# Power.net
KiCad netlist of a schematic drawn in Altium Designer
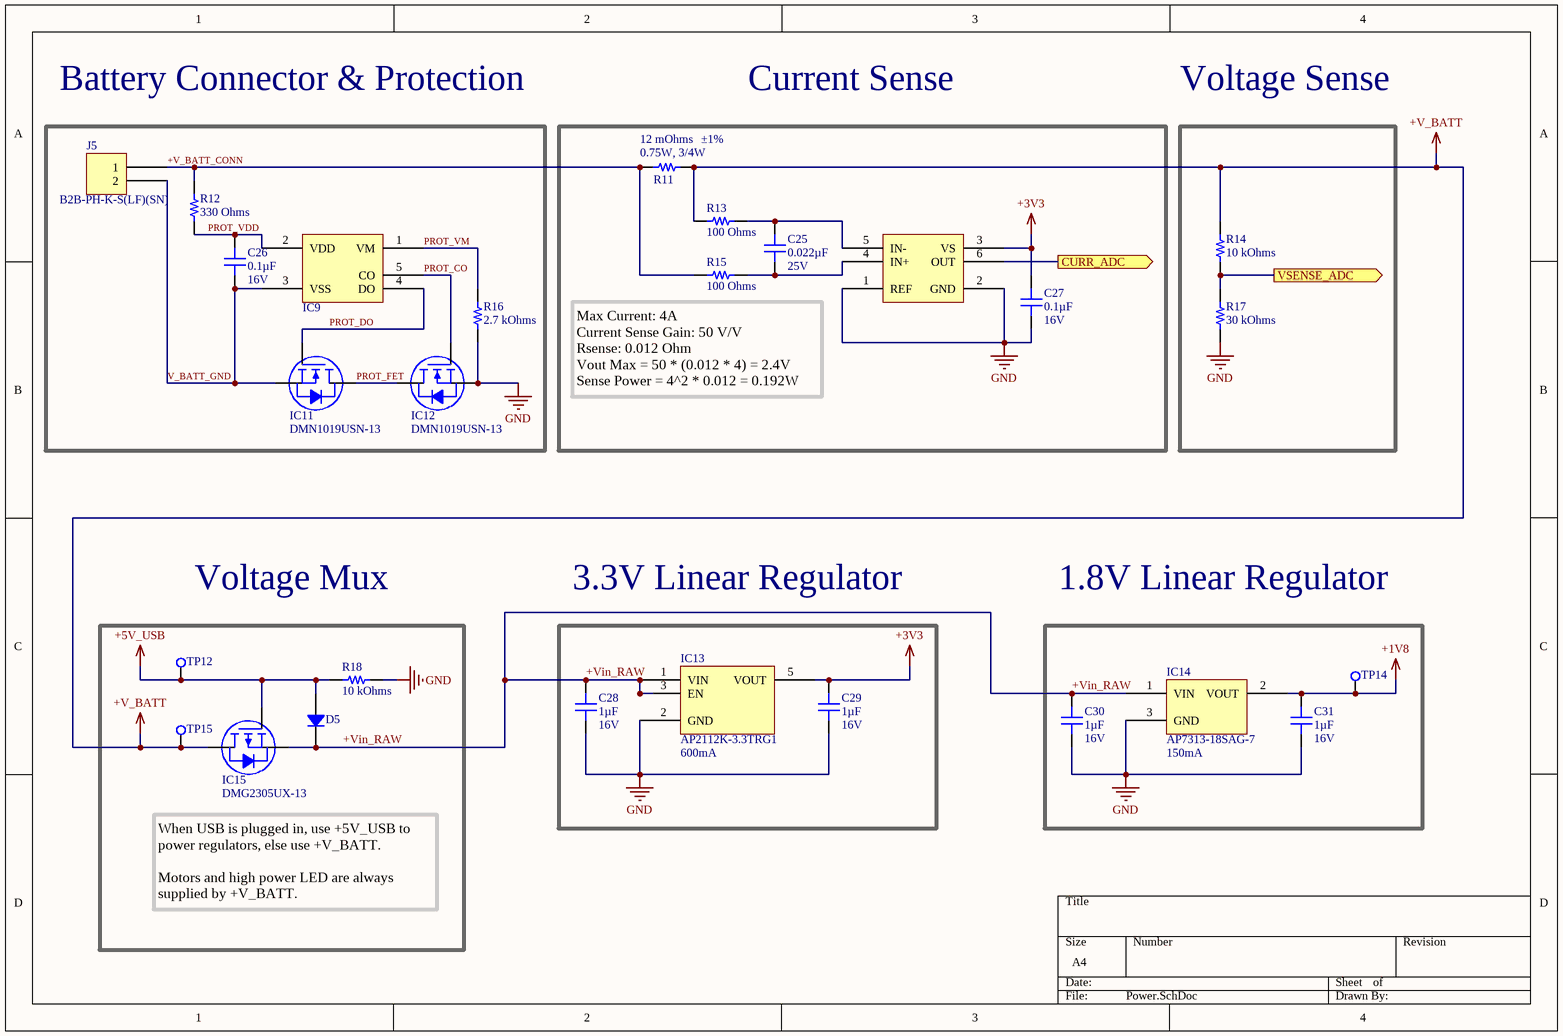
[diagram p0: Power.SchDoc]

(export (version "E")
  (design (tool "Eeschema 10.0.6"))
  (components
    (comp (ref "C25")
      (value "0.022µF")
      (footprint "CAP 0603_1608")
      (description "CAP CER 0.022UF 25V X7R 0603")
      (fields
        (field (name "PART NUMBER") "CC0603JRX7R8BB223")
        (field (name "MANUFACTURER") "Yageo")
        (field (name "VOLTAGE - RATED") "25V")
      )
      (libsource (lib "Celestial Altium Library - altium_library") (part "Capacitor"))
    )
    (comp (ref "C26")
      (value "0.1µF")
      (footprint "CAP 0603_1608")
      (description "CAP CER 0.1UF 16V X7R 0603")
      (fields
        (field (name "PART NUMBER") "CC0603KRX7R7BB104")
        (field (name "MANUFACTURER") "Yageo")
        (field (name "VOLTAGE - RATED") "16V")
      )
      (libsource (lib "Celestial Altium Library - altium_library") (part "Capacitor"))
    )
    (comp (ref "C27")
      (value "0.1µF")
      (footprint "CAP 0603_1608")
      (description "CAP CER 0.1UF 16V X7R 0603")
      (fields
        (field (name "PART NUMBER") "CC0603KRX7R7BB104")
        (field (name "MANUFACTURER") "Yageo")
        (field (name "VOLTAGE - RATED") "16V")
      )
      (libsource (lib "Celestial Altium Library - altium_library") (part "Capacitor"))
    )
    (comp (ref "C28")
      (value "1µF")
      (footprint "CAP 0603_1608")
      (description "CAP CER 1UF 16V X5R 0603")
      (fields
        (field (name "PART NUMBER") "CC0603MRX5R7BB105")
        (field (name "MANUFACTURER") "Yageo")
        (field (name "VOLTAGE - RATED") "16V")
      )
      (libsource (lib "Celestial Altium Library - altium_library") (part "Capacitor"))
    )
    (comp (ref "C29")
      (value "1µF")
      (footprint "CAP 0603_1608")
      (description "CAP CER 1UF 16V X5R 0603")
      (fields
        (field (name "PART NUMBER") "CC0603MRX5R7BB105")
        (field (name "MANUFACTURER") "Yageo")
        (field (name "VOLTAGE - RATED") "16V")
      )
      (libsource (lib "Celestial Altium Library - altium_library") (part "Capacitor"))
    )
    (comp (ref "C30")
      (value "1µF")
      (footprint "CAP 0603_1608")
      (description "CAP CER 1UF 16V X5R 0603")
      (fields
        (field (name "PART NUMBER") "CC0603MRX5R7BB105")
        (field (name "MANUFACTURER") "Yageo")
        (field (name "VOLTAGE - RATED") "16V")
      )
      (libsource (lib "Celestial Altium Library - altium_library") (part "Capacitor"))
    )
    (comp (ref "C31")
      (value "1µF")
      (footprint "CAP 0603_1608")
      (description "CAP CER 1UF 16V X5R 0603")
      (fields
        (field (name "PART NUMBER") "CC0603MRX5R7BB105")
        (field (name "MANUFACTURER") "Yageo")
        (field (name "VOLTAGE - RATED") "16V")
      )
      (libsource (lib "Celestial Altium Library - altium_library") (part "Capacitor"))
    )
    (comp (ref "D5")
      (value "SS1FL3-M3/H")
      (footprint "SMF DO-219AB")
      (description "DIODE SCHOTTKY 30V 1A DO-219AB")
      (fields (field (name "MANUFACTURER") "Vishay Semiconductor Diodes Division"))
      (libsource (lib "Celestial Altium Library - altium_library") (part "Diode"))
    )
    (comp (ref "IC9")
      (value "AP9101CK-AHTRG1")
      (footprint "SOT95P285X140-5N")
      (description "IC BATT PROT LI-ION 1-CELL SOT25")
      (fields (field (name "MANUFACTURER") "Diodes"))
      (libsource (lib "Drone") (part "AP9101CK-AHTRG1"))
    )
    (comp (ref "IC10")
      (value "INA190A2IDCKT")
      (footprint "SOT65P210X110-6N")
      (description "Precision Current-Sense Amplifier Bi-Directional 1-Channel 50V/V 1.7V to 5.5V 6-Pin SC-70 T/R")
      (fields (field (name "MANUFACTURER") "Texas Instruments"))
      (libsource (lib "Drone") (part "INA190A2IDCKT"))
    )
    (comp (ref "IC11")
      (value "DMN1019USN-13")
      (footprint "DIODES SOT-23-3")
      (description "MOSFET N-CH 12V 9.3A SC59")
      (fields (field (name "MANUFACTURER") "Diodes Incorporated"))
      (libsource (lib "Celestial Altium Library - altium_library") (part "DIODES INC MOSFET N-CH SOT-23-3"))
    )
    (comp (ref "IC12")
      (value "DMN1019USN-13")
      (footprint "DIODES SOT-23-3")
      (description "MOSFET N-CH 12V 9.3A SC59")
      (fields (field (name "MANUFACTURER") "Diodes Incorporated"))
      (libsource (lib "") (part "DIODES INC MOSFET N-CH SOT-23-3_1"))
    )
    (comp (ref "IC13")
      (value "AP2112K-3.3TRG1")
      (footprint "DIODES SOT-23-5 W5")
      (description "IC REG LINEAR 3.3V 600MA SOT25")
      (fields (field (name "CURRENT - OUTPUT") "600mA") (field (name "MANUFACTURER") "Diodes Incorporated"))
      (libsource (lib "Celestial Altium Library - altium_library") (part "DIODES INC AP2112K"))
    )
    (comp (ref "IC14")
      (value "AP7313-18SAG-7")
      (footprint "DIODES SOT-23-3")
      (description "IC REG LINEAR 1.8V 150MA SOT23-3")
      (fields (field (name "CURRENT - OUTPUT") "150mA") (field (name "MANUFACTURER") "Diodes Incorporated"))
      (libsource (lib "Celestial Altium Library - altium_library") (part "Diodes Inc AP7313"))
    )
    (comp (ref "IC15")
      (value "DMG2305UX-13")
      (footprint "DIODES SOT-23-3")
      (description "MOSFET P-CH 20V 4.2A SOT23")
      (fields (field (name "MANUFACTURER") "Diodes Incorporated"))
      (libsource (lib "Celestial Altium Library - altium_library") (part "DIODES MOSFET P-CH SOT-23-3"))
    )
    (comp (ref "J5")
      (value "B2B-PH-K-S(LF)(SN)")
      (footprint "JST B2B-PH-K")
      (description "CONN HEADER VERT 2POS 2MM")
      (fields (field (name "MANUFACTURER") "JST Sales America Inc."))
      (libsource (lib "Celestial Altium Library - altium_library") (part "2 Pin"))
    )
    (comp (ref "R11")
      (value "12 mOhms")
      (footprint "STACKPOLE CSR1206")
      (description "RES 0.012 OHM 1% 3/4W 1206")
      (fields
        (field (name "PART NUMBER") "KRL1632E-M-R012-F-T5")
        (field (name "MANUFACTURER") "Susumu")
        (field (name "POWER (WATTS)") "0.75W, 3/4W")
        (field (name "TOLERANCE") "±1%")
      )
      (libsource (lib "Celestial Altium Library - altium_library") (part "Resistor"))
    )
    (comp (ref "R12")
      (value "330 Ohms")
      (footprint "RES 0603_1608")
      (description "RES SMD 330 OHM 1% 1/10W 0603")
      (fields (field (name "PART NUMBER") "AC0603FR-07330RL") (field (name "MANUFACTURER") "Yageo"))
      (libsource (lib "Celestial Altium Library - altium_library") (part "Resistor"))
    )
    (comp (ref "R13")
      (value "100 Ohms")
      (footprint "RES 0603_1608")
      (description "RES SMD 100 OHM 1% 1/10W 0603")
      (fields (field (name "PART NUMBER") "AC0603FR-07100RL") (field (name "MANUFACTURER") "Yageo"))
      (libsource (lib "Celestial Altium Library - altium_library") (part "Resistor"))
    )
    (comp (ref "R14")
      (value "10 kOhms")
      (footprint "RES 0603_1608")
      (description "RES SMD 10K OHM 1% 1/10W 0603")
      (fields (field (name "PART NUMBER") "AC0603FR-0710KL") (field (name "MANUFACTURER") "Yageo"))
      (libsource (lib "Celestial Altium Library - altium_library") (part "Resistor"))
    )
    (comp (ref "R15")
      (value "100 Ohms")
      (footprint "RES 0603_1608")
      (description "RES SMD 100 OHM 1% 1/10W 0603")
      (fields (field (name "PART NUMBER") "AC0603FR-07100RL") (field (name "MANUFACTURER") "Yageo"))
      (libsource (lib "Celestial Altium Library - altium_library") (part "Resistor"))
    )
    (comp (ref "R16")
      (value "2.7 kOhms")
      (footprint "RES 0603_1608")
      (description "RES SMD 2.7K OHM 1% 1/10W 0603")
      (fields (field (name "PART NUMBER") "AC0603FR-072K7L") (field (name "MANUFACTURER") "Yageo"))
      (libsource (lib "Celestial Altium Library - altium_library") (part "Resistor"))
    )
    (comp (ref "R17")
      (value "30 kOhms")
      (footprint "RES 0603_1608")
      (description "RES SMD 30K OHM 1% 1/10W 0603")
      (fields (field (name "PART NUMBER") "CR0603-FX-3002ELF") (field (name "MANUFACTURER") "Bourns Inc."))
      (libsource (lib "Celestial Altium Library - altium_library") (part "Resistor"))
    )
    (comp (ref "R18")
      (value "10 kOhms")
      (footprint "RES 0603_1608")
      (description "RES SMD 10K OHM 1% 1/10W 0603")
      (fields (field (name "PART NUMBER") "AC0603FR-0710KL") (field (name "MANUFACTURER") "Yageo"))
      (libsource (lib "Celestial Altium Library - altium_library") (part "Resistor"))
    )
    (comp (ref "TP12")
      (value "TestPoint")
      (footprint "TestPoint")
      (libsource (lib "Drone") (part "TestPoint"))
    )
    (comp (ref "TP14")
      (value "TestPoint")
      (footprint "TestPoint")
      (libsource (lib "Drone") (part "TestPoint"))
    )
    (comp (ref "TP15")
      (value "TestPoint")
      (footprint "TestPoint")
      (libsource (lib "Drone") (part "TestPoint"))
    )
  )
  (nets
    (net (code "1") (name "+1V8") (class "Default")
      (node (ref "C31") (pin "2") (pinfunction "2_2") (pintype "passive"))
      (node (ref "IC14") (pin "2") (pinfunction "VOUT_2") (pintype "passive"))
      (node (ref "TP14") (pin "1") (pinfunction "1_1") (pintype "passive"))
    )
    (net (code "2") (name "+3V3") (class "Default")
      (node (ref "C27") (pin "1") (pinfunction "1_1") (pintype "passive"))
      (node (ref "C29") (pin "2") (pinfunction "2_2") (pintype "passive"))
      (node (ref "IC10") (pin "3") (pinfunction "VS_3") (pintype "passive"))
      (node (ref "IC13") (pin "5") (pinfunction "VOUT_5") (pintype "passive"))
    )
    (net (code "3") (name "+5V_USB") (class "Default")
      (node (ref "D5") (pin "1") (pinfunction "1_1") (pintype "passive"))
      (node (ref "IC15") (pin "1") (pinfunction "G_1") (pintype "passive"))
      (node (ref "R18") (pin "2") (pinfunction "2_2") (pintype "passive"))
      (node (ref "TP12") (pin "1") (pinfunction "1_1") (pintype "passive"))
    )
    (net (code "4") (name "+V_BATT") (class "Default")
      (node (ref "IC15") (pin "3") (pinfunction "D_3") (pintype "passive"))
      (node (ref "R11") (pin "2") (pinfunction "2_2") (pintype "passive"))
      (node (ref "R13") (pin "2") (pinfunction "2_2") (pintype "passive"))
      (node (ref "R14") (pin "1") (pinfunction "1_1") (pintype "passive"))
      (node (ref "TP15") (pin "1") (pinfunction "1_1") (pintype "passive"))
    )
    (net (code "5") (name "/+V_BATT_CONN") (class "Default")
      (node (ref "J5") (pin "1") (pinfunction "1_1") (pintype "passive"))
      (node (ref "R11") (pin "1") (pinfunction "1_1") (pintype "passive"))
      (node (ref "R12") (pin "2") (pinfunction "2_2") (pintype "passive"))
      (node (ref "R15") (pin "2") (pinfunction "2_2") (pintype "passive"))
    )
    (net (code "6") (name "/+Vin_RAW") (class "Default")
      (node (ref "C28") (pin "2") (pinfunction "2_2") (pintype "passive"))
      (node (ref "C30") (pin "2") (pinfunction "2_2") (pintype "passive"))
      (node (ref "D5") (pin "2") (pinfunction "2_2") (pintype "passive"))
      (node (ref "IC13") (pin "1") (pinfunction "VIN_1") (pintype "passive"))
      (node (ref "IC13") (pin "3") (pinfunction "EN_3") (pintype "passive"))
      (node (ref "IC14") (pin "1") (pinfunction "VIN_1") (pintype "passive"))
      (node (ref "IC15") (pin "2") (pinfunction "S_2") (pintype "passive"))
    )
    (net (code "7") (name "/CURR_ADC") (class "Default")
      (node (ref "IC10") (pin "6") (pinfunction "OUT_6") (pintype "passive"))
    )
    (net (code "8") (name "/PROT_CO") (class "Default")
      (node (ref "IC12") (pin "1") (pinfunction "G_1") (pintype "passive"))
      (node (ref "IC9") (pin "5") (pinfunction "CO_5") (pintype "passive"))
    )
    (net (code "9") (name "/PROT_DO") (class "Default")
      (node (ref "IC11") (pin "1") (pinfunction "G_1") (pintype "passive"))
      (node (ref "IC9") (pin "4") (pinfunction "DO_4") (pintype "passive"))
    )
    (net (code "10") (name "/PROT_FET") (class "Default")
      (node (ref "IC11") (pin "3") (pinfunction "D_3") (pintype "passive"))
      (node (ref "IC12") (pin "3") (pinfunction "D_3") (pintype "passive"))
    )
    (net (code "11") (name "/PROT_VDD") (class "Default")
      (node (ref "C26") (pin "2") (pinfunction "2_2") (pintype "passive"))
      (node (ref "IC9") (pin "2") (pinfunction "VDD_2") (pintype "passive"))
      (node (ref "R12") (pin "1") (pinfunction "1_1") (pintype "passive"))
    )
    (net (code "12") (name "/PROT_VM") (class "Default")
      (node (ref "IC9") (pin "1") (pinfunction "VM_1") (pintype "passive"))
      (node (ref "R16") (pin "2") (pinfunction "2_2") (pintype "passive"))
    )
    (net (code "13") (name "/VSENSE_ADC") (class "Default")
      (node (ref "R14") (pin "2") (pinfunction "2_2") (pintype "passive"))
      (node (ref "R17") (pin "2") (pinfunction "2_2") (pintype "passive"))
    )
    (net (code "14") (name "/V_BATT_GND") (class "Default")
      (node (ref "C26") (pin "1") (pinfunction "1_1") (pintype "passive"))
      (node (ref "IC11") (pin "2") (pinfunction "S_2") (pintype "passive"))
      (node (ref "IC9") (pin "3") (pinfunction "VSS_3") (pintype "passive"))
      (node (ref "J5") (pin "2") (pinfunction "2_2") (pintype "passive"))
    )
    (net (code "15") (name "GND") (class "Default")
      (node (ref "C27") (pin "2") (pinfunction "2_2") (pintype "passive"))
      (node (ref "C28") (pin "1") (pinfunction "1_1") (pintype "passive"))
      (node (ref "C29") (pin "1") (pinfunction "1_1") (pintype "passive"))
      (node (ref "C30") (pin "1") (pinfunction "1_1") (pintype "passive"))
      (node (ref "C31") (pin "1") (pinfunction "1_1") (pintype "passive"))
      (node (ref "IC10") (pin "1") (pinfunction "REF_1") (pintype "passive"))
      (node (ref "IC10") (pin "2") (pinfunction "GND_2") (pintype "passive"))
      (node (ref "IC12") (pin "2") (pinfunction "S_2") (pintype "passive"))
      (node (ref "IC13") (pin "2") (pinfunction "GND_2") (pintype "passive"))
      (node (ref "IC14") (pin "3") (pinfunction "GND_3") (pintype "passive"))
      (node (ref "R16") (pin "1") (pinfunction "1_1") (pintype "passive"))
      (node (ref "R17") (pin "1") (pinfunction "1_1") (pintype "passive"))
      (node (ref "R18") (pin "1") (pinfunction "1_1") (pintype "passive"))
    )
    (net (code "16") (name "Net-(IC10-IN+)") (class "Default")
      (node (ref "C25") (pin "1") (pinfunction "1_1") (pintype "passive"))
      (node (ref "IC10") (pin "4") (pinfunction "IN+_4") (pintype "passive"))
      (node (ref "R15") (pin "1") (pinfunction "1_1") (pintype "passive"))
    )
    (net (code "17") (name "Net-(IC10-IN-)") (class "Default")
      (node (ref "C25") (pin "2") (pinfunction "2_2") (pintype "passive"))
      (node (ref "IC10") (pin "5") (pinfunction "IN-_5") (pintype "passive"))
      (node (ref "R13") (pin "1") (pinfunction "1_1") (pintype "passive"))
    )
  )
)
